# efr32_lcd_hmi.net
KiCad netlist of a schematic drawn in Altium Designer
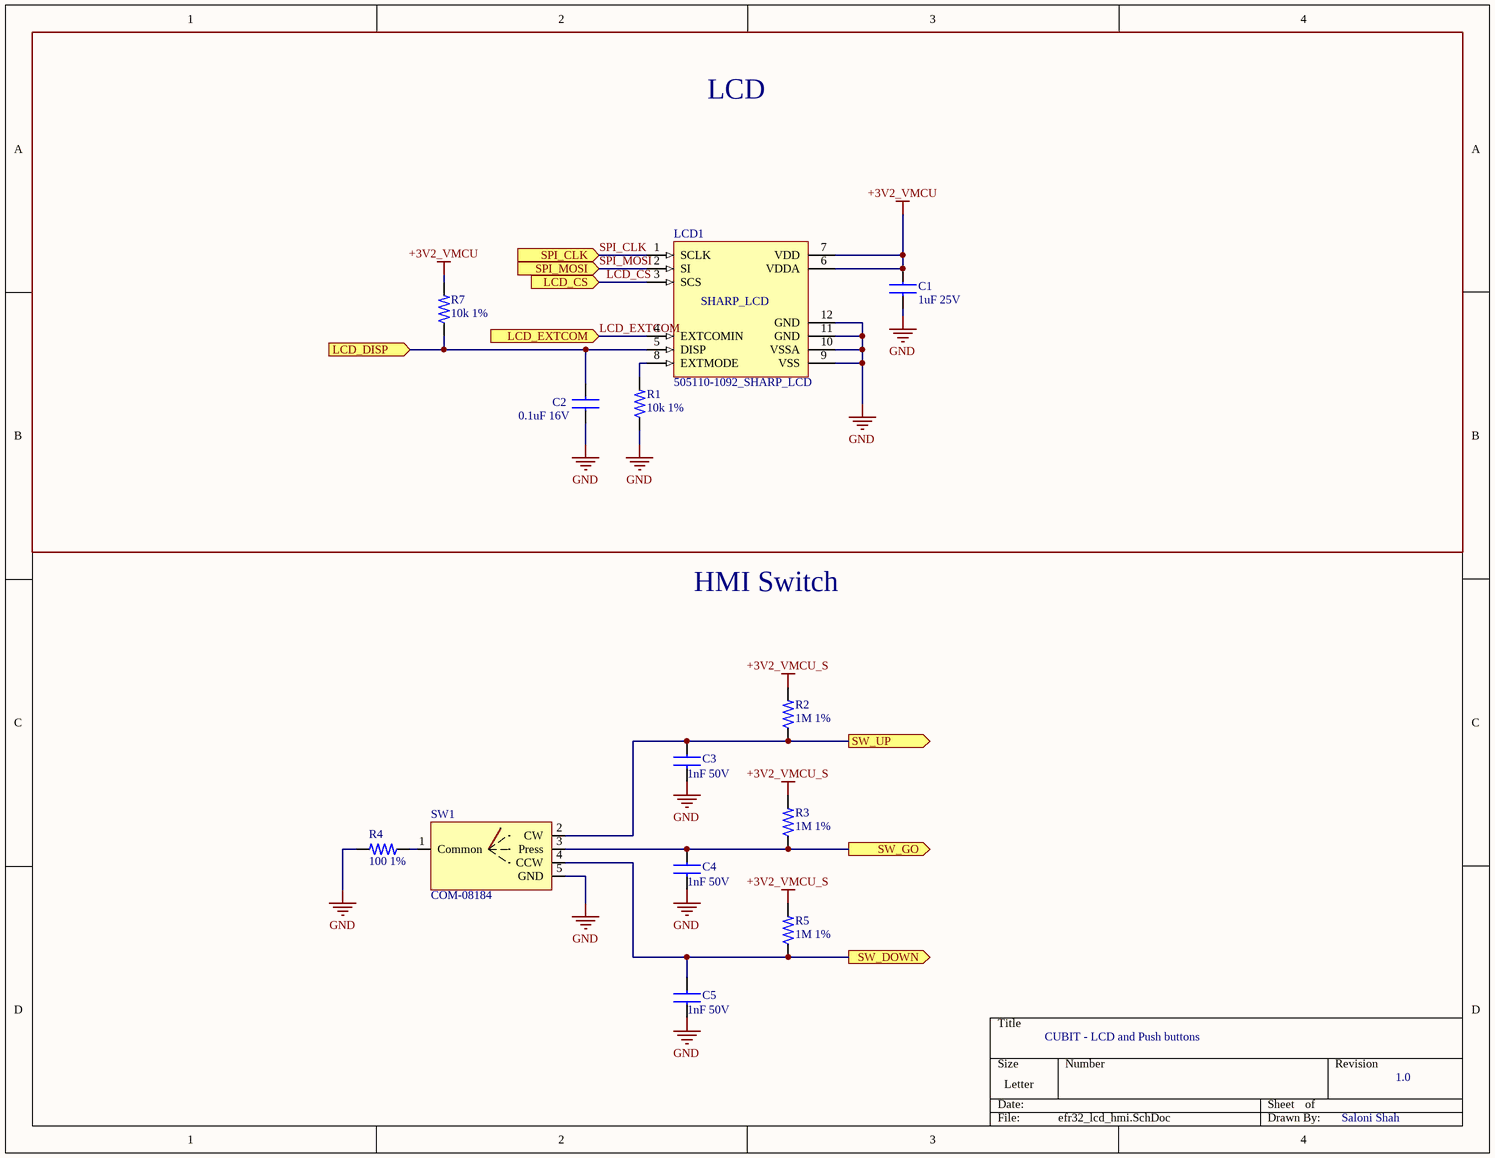
[diagram p0: efr32_lcd_hmi.SchDoc]

(export (version "E")
  (design (tool "Eeschema 10.0.6"))
  (components
    (comp (ref "C1")
      (value "1uF 25V")
      (footprint "CAP_0805_02X125")
      (description "Cap 1 µF ±10% 25V Ceramic Capacitor X5R 0805 (2012 Metric)")
      (fields
        (field (name "MANUFACTURER") "Murata")
        (field (name "MANUFACTURER PART NUMBER") "GRM216R61E105KA12D")
      )
      (libsource (lib "LPEDT_proj_lib") (part "GRM216R61E105KA12D"))
    )
    (comp (ref "C2")
      (value "0.1uF 16V")
      (footprint "CAP_0603_1MM")
      (description "Cap Ceramic 0.1uF 16V X7R 10% SMD 0603 125°C Paper T/R")
      (fields
        (field (name "MANUFACTURER") "KEMET")
        (field (name "MANUFACTURER PART NUMBER") "C0805C104K4RACAUTO")
      )
      (libsource (lib "LPEDT_proj_lib") (part "C0805C104K4RACAUTO"))
    )
    (comp (ref "C3")
      (value "1nF 50V")
      (footprint "CAP_0805_02X125")
      (description "1nF ±10% 50V X7R 0805")
      (fields
        (field (name "MANUFACTURER") "Samsung")
        (field (name "MANUFACTURER PART NUMBER") "CL21B102KBANFNC")
      )
      (libsource (lib "LPEDT_proj_lib") (part "CL21B102KBANFNC"))
    )
    (comp (ref "C4")
      (value "1nF 50V")
      (footprint "CAP_0805_02X125")
      (description "1nF ±10% 50V X7R 0805")
      (fields
        (field (name "MANUFACTURER") "Samsung")
        (field (name "MANUFACTURER PART NUMBER") "CL21B102KBANFNC")
      )
      (libsource (lib "LPEDT_proj_lib") (part "CL21B102KBANFNC"))
    )
    (comp (ref "C5")
      (value "1nF 50V")
      (footprint "CAP_0805_02X125")
      (description "1nF ±10% 50V X7R 0805")
      (fields
        (field (name "MANUFACTURER") "Samsung")
        (field (name "MANUFACTURER PART NUMBER") "CL21B102KBANFNC")
      )
      (libsource (lib "LPEDT_proj_lib") (part "CL21B102KBANFNC"))
    )
    (comp (ref "LCD1")
      (value "505110-1092_SHARP_LCD")
      (footprint "SHARP_LCD")
      (description "FFC/FPC Connector, 10 Contact(s), 1 Row(s), Female, Right Angle, Surface Mount Terminal")
      (fields (field (name "MANUFACTURER") "Molex") (field (name "MANUFACTURER PART NUMBER") "505110-1092"))
      (libsource (lib "LPEDT_proj_lib") (part "505110-1092_SHARP_LCD"))
    )
    (comp (ref "R1")
      (value "10k 1%")
      (footprint "2_Chip_0603_RMCF")
      (description "Res 10K Ohm 1% 1/10W ±100ppm/°C Molded SMD SMD Paper T/R")
      (fields
        (field (name "MANUFACTURER") "Stackpole Electronics")
        (field (name "MANUFACTURER PART NUMBER") "RMCF0603FT10K0")
      )
      (libsource (lib "LPEDT_proj_lib") (part "RMCF0603FT10K0"))
    )
    (comp (ref "R2")
      (value "1M 1%")
      (footprint "2_Chip_0603_RMCF")
      (description "Res 1M Ohm 1% 1/10W ±100ppm/°C Molded SMD Paper T/R")
      (fields
        (field (name "MANUFACTURER") "Stackpole Electronics")
        (field (name "MANUFACTURER PART NUMBER") "RMCF0603FT1M00")
      )
      (libsource (lib "LPEDT_proj_lib") (part "RMCF0603FT1M00"))
    )
    (comp (ref "R3")
      (value "1M 1%")
      (footprint "2_Chip_0603_RMCF")
      (description "Res 1M Ohm 1% 1/10W ±100ppm/°C Molded SMD Paper T/R")
      (fields
        (field (name "MANUFACTURER") "Stackpole Electronics")
        (field (name "MANUFACTURER PART NUMBER") "RMCF0603FT1M00")
      )
      (libsource (lib "LPEDT_proj_lib") (part "RMCF0603FT1M00"))
    )
    (comp (ref "R4")
      (value "100 1%")
      (footprint "2_Chip_0603_RMCF")
      (description "Res 100 Ohm 1% 1/10W ±100ppm/°C Molded SMD SMD Paper T/R")
      (fields
        (field (name "MANUFACTURER") "Stackpole Electronics")
        (field (name "MANUFACTURER PART NUMBER") "RMCF0603FT100R")
      )
      (libsource (lib "LPEDT_proj_lib") (part "RMCF0603FT100R"))
    )
    (comp (ref "R5")
      (value "1M 1%")
      (footprint "2_Chip_0603_RMCF")
      (description "Res 1M Ohm 1% 1/10W ±100ppm/°C Molded SMD Paper T/R")
      (fields
        (field (name "MANUFACTURER") "Stackpole Electronics")
        (field (name "MANUFACTURER PART NUMBER") "RMCF0603FT1M00")
      )
      (libsource (lib "LPEDT_proj_lib") (part "RMCF0603FT1M00"))
    )
    (comp (ref "R7")
      (value "10k 1%")
      (footprint "2_Chip_0603_RMCF")
      (description "Res 10K Ohm 1% 1/10W ±100ppm/°C Molded SMD SMD Paper T/R")
      (fields
        (field (name "MANUFACTURER") "Stackpole Electronics")
        (field (name "MANUFACTURER PART NUMBER") "RMCF0603FT10K0")
      )
      (libsource (lib "LPEDT_proj_lib") (part "RMCF0603FT10K0"))
    )
    (comp (ref "SW1")
      (value "COM-08184")
      (footprint "Navigation_switch")
      (description "Surface Mount Navigation Switch")
      (fields (field (name "MANUFACTURER") "SparkFun"))
      (libsource (lib "LPEDT_proj_lib") (part "COM-08184"))
    )
  )
  (nets
    (net (code "1") (name "+3V2_VMCU") (class "Default")
      (node (ref "C1") (pin "1") (pinfunction "1_1") (pintype "passive"))
      (node (ref "LCD1") (pin "6") (pinfunction "VDDA_6") (pintype "power_in"))
      (node (ref "LCD1") (pin "7") (pinfunction "VDD_7") (pintype "power_in"))
      (node (ref "R7") (pin "2") (pinfunction "2_2") (pintype "passive"))
    )
    (net (code "2") (name "+3V2_VMCU_S") (class "Default")
      (node (ref "R2") (pin "2") (pinfunction "2_2") (pintype "passive"))
      (node (ref "R3") (pin "2") (pinfunction "2_2") (pintype "passive"))
      (node (ref "R5") (pin "2") (pinfunction "2_2") (pintype "passive"))
    )
    (net (code "3") (name "/LCD_CS") (class "Default")
      (node (ref "LCD1") (pin "3") (pinfunction "SCS_3") (pintype "input"))
    )
    (net (code "4") (name "/LCD_DISP") (class "Default")
      (node (ref "C2") (pin "1") (pinfunction "1_1") (pintype "passive"))
      (node (ref "LCD1") (pin "5") (pinfunction "DISP_5") (pintype "input"))
      (node (ref "R7") (pin "1") (pinfunction "1_1") (pintype "passive"))
    )
    (net (code "5") (name "/LCD_EXTCOM") (class "Default")
      (node (ref "LCD1") (pin "4") (pinfunction "EXTCOMIN_4") (pintype "input"))
    )
    (net (code "6") (name "/SPI_CLK") (class "Default")
      (node (ref "LCD1") (pin "1") (pinfunction "SCLK_1") (pintype "input"))
    )
    (net (code "7") (name "/SPI_MOSI") (class "Default")
      (node (ref "LCD1") (pin "2") (pinfunction "SI_2") (pintype "input"))
    )
    (net (code "8") (name "/SW_DOWN") (class "Default")
      (node (ref "C5") (pin "1") (pinfunction "1_1") (pintype "passive"))
      (node (ref "R5") (pin "1") (pinfunction "1_1") (pintype "passive"))
      (node (ref "SW1") (pin "4") (pinfunction "CCW_4") (pintype "passive"))
    )
    (net (code "9") (name "/SW_GO") (class "Default")
      (node (ref "C4") (pin "1") (pinfunction "1_1") (pintype "passive"))
      (node (ref "R3") (pin "1") (pinfunction "1_1") (pintype "passive"))
      (node (ref "SW1") (pin "3") (pinfunction "Press_3") (pintype "passive"))
    )
    (net (code "10") (name "/SW_UP") (class "Default")
      (node (ref "C3") (pin "1") (pinfunction "1_1") (pintype "passive"))
      (node (ref "R2") (pin "1") (pinfunction "1_1") (pintype "passive"))
      (node (ref "SW1") (pin "2") (pinfunction "CW_2") (pintype "passive"))
    )
    (net (code "11") (name "GND") (class "Default")
      (node (ref "C1") (pin "2") (pinfunction "2_2") (pintype "passive"))
      (node (ref "C2") (pin "2") (pinfunction "2_2") (pintype "passive"))
      (node (ref "C3") (pin "2") (pinfunction "2_2") (pintype "passive"))
      (node (ref "C4") (pin "2") (pinfunction "2_2") (pintype "passive"))
      (node (ref "C5") (pin "2") (pinfunction "2_2") (pintype "passive"))
      (node (ref "LCD1") (pin "10") (pinfunction "VSSA_10") (pintype "power_in"))
      (node (ref "LCD1") (pin "11") (pinfunction "GND_11") (pintype "power_in"))
      (node (ref "LCD1") (pin "12") (pinfunction "GND_12") (pintype "power_in"))
      (node (ref "LCD1") (pin "9") (pinfunction "VSS_9") (pintype "power_in"))
      (node (ref "R1") (pin "1") (pinfunction "1_1") (pintype "passive"))
      (node (ref "R4") (pin "2") (pinfunction "2_2") (pintype "passive"))
      (node (ref "SW1") (pin "5") (pinfunction "GND_5") (pintype "power_in"))
    )
    (net (code "12") (name "Net-(LCD1-EXTMODE)") (class "Default")
      (node (ref "LCD1") (pin "8") (pinfunction "EXTMODE_8") (pintype "input"))
      (node (ref "R1") (pin "2") (pinfunction "2_2") (pintype "passive"))
    )
    (net (code "13") (name "Net-(SW1-Common)") (class "Default")
      (node (ref "R4") (pin "1") (pinfunction "1_1") (pintype "passive"))
      (node (ref "SW1") (pin "1") (pinfunction "Common_1") (pintype "power_in"))
    )
  )
)
